# W076Dclone.net
KiCad netlist of a schematic drawn in EAGLE
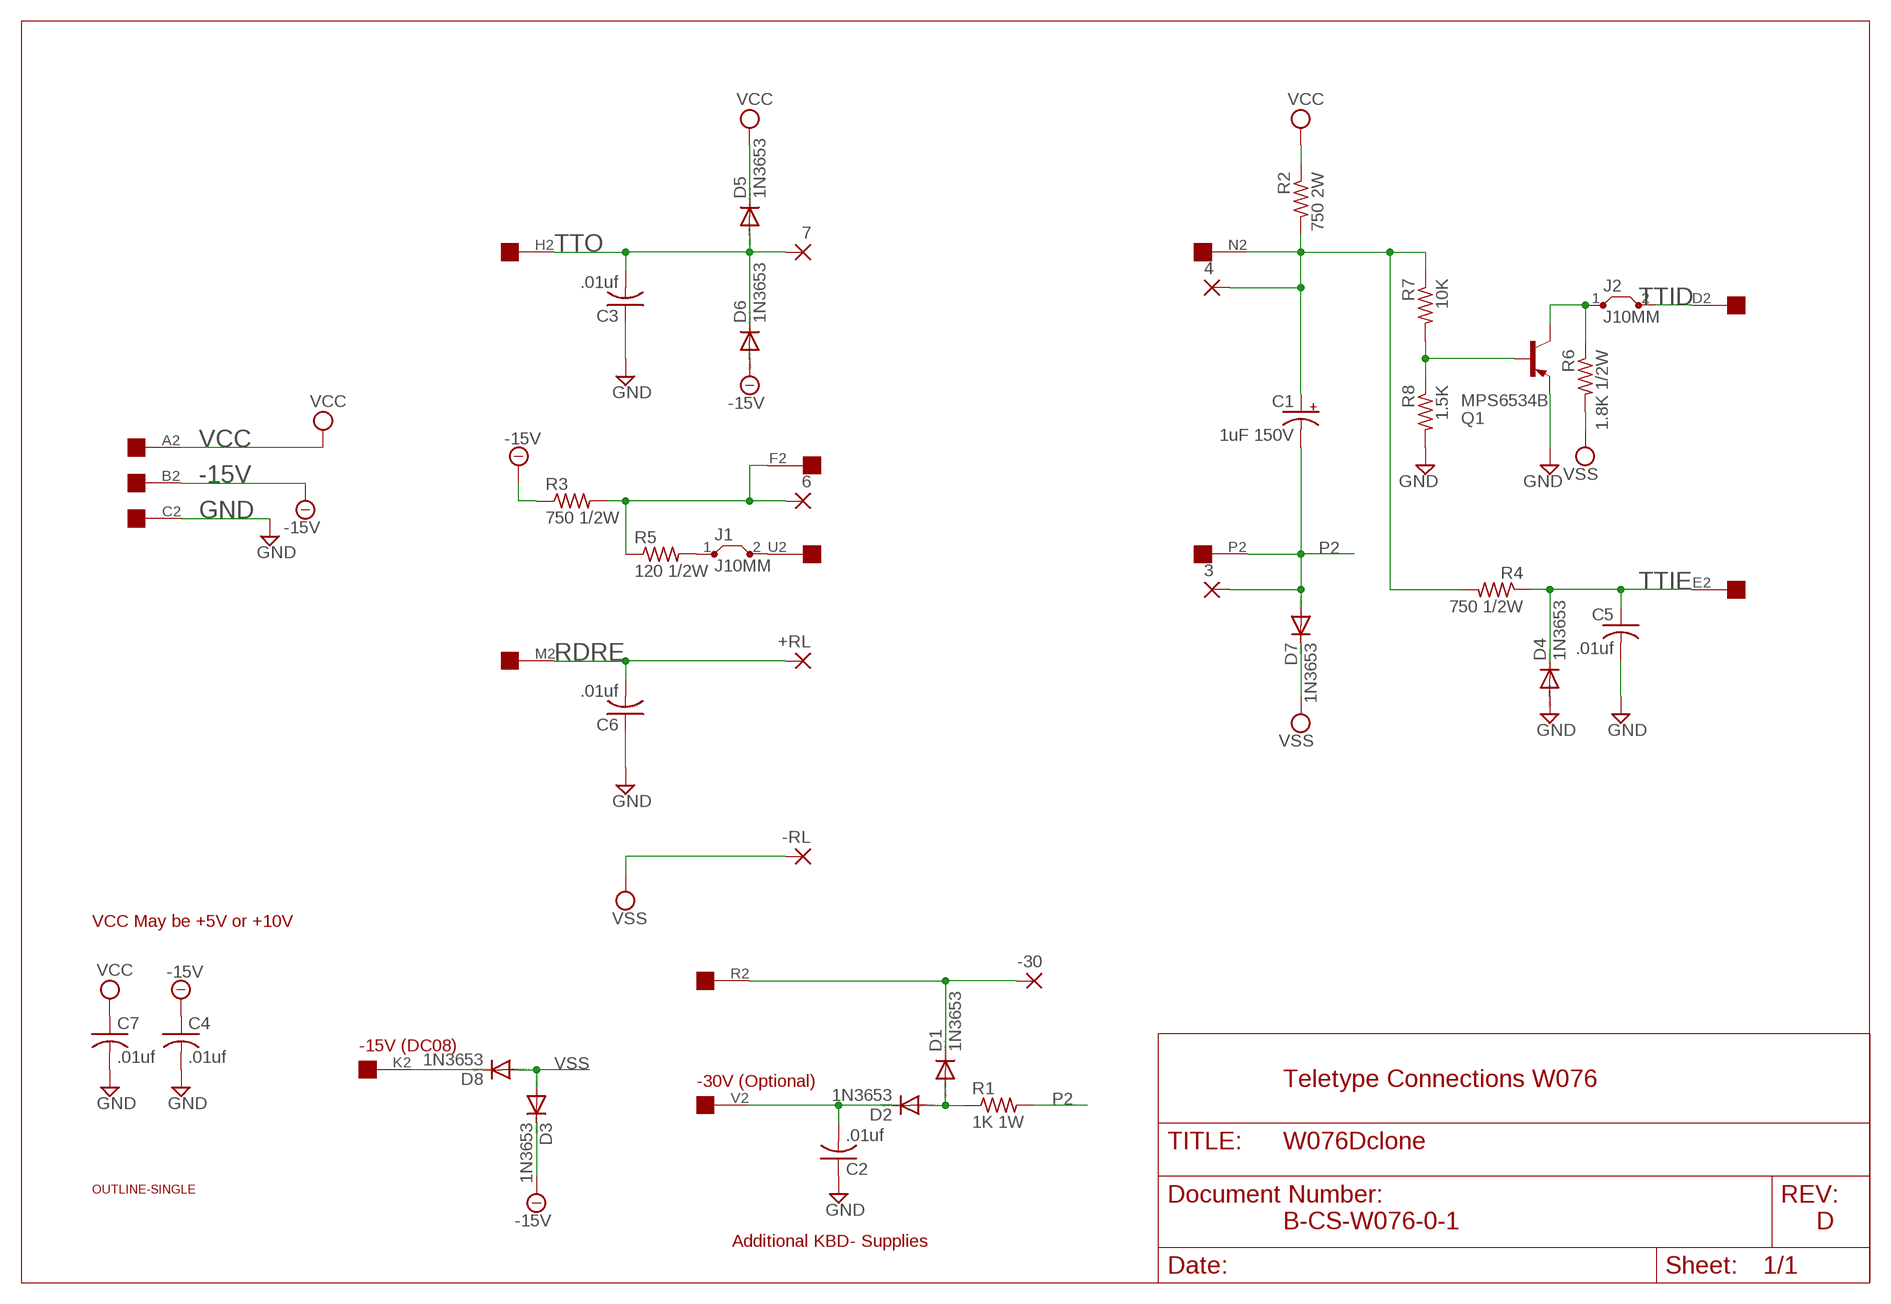
[diagram p0: schematic, sheet 1]

(export (version "E")
  (design (tool "Eeschema 10.0.6"))
  (components
    (comp (ref "+RL")
      (value "2,54/1,0")
      (footprint "eagle-import:2,54_1,0")
      (libsource (lib "eagle-import") (part "2,54/1,0"))
    )
    (comp (ref "-30")
      (value "2,54/1,0")
      (footprint "eagle-import:2,54_1,0")
      (libsource (lib "eagle-import") (part "2,54/1,0"))
    )
    (comp (ref "-RL")
      (value "2,54/1,0")
      (footprint "eagle-import:2,54_1,0")
      (libsource (lib "eagle-import") (part "2,54/1,0"))
    )
    (comp (ref "3")
      (value "2,54/1,0")
      (footprint "eagle-import:2,54_1,0")
      (libsource (lib "eagle-import") (part "2,54/1,0"))
    )
    (comp (ref "4")
      (value "2,54/1,0")
      (footprint "eagle-import:2,54_1,0")
      (libsource (lib "eagle-import") (part "2,54/1,0"))
    )
    (comp (ref "6")
      (value "2,54/1,0")
      (footprint "eagle-import:2,54_1,0")
      (libsource (lib "eagle-import") (part "2,54/1,0"))
    )
    (comp (ref "7")
      (value "2,54/1,0")
      (footprint "eagle-import:2,54_1,0")
      (libsource (lib "eagle-import") (part "2,54/1,0"))
    )
    (comp (ref "C1")
      (value "1uF 150V")
      (footprint "eagle-import:E25-9")
      (libsource (lib "eagle-import") (part "CPOL-USE25-9AXIAL"))
    )
    (comp (ref "C2")
      (value ".01uf")
      (footprint "eagle-import:C050-025X075")
      (libsource (lib "eagle-import") (part "C-US050-025X075"))
    )
    (comp (ref "C3")
      (value ".01uf")
      (footprint "eagle-import:C050-025X075")
      (libsource (lib "eagle-import") (part "C-US050-025X075"))
    )
    (comp (ref "C4")
      (value ".01uf")
      (footprint "eagle-import:C050-025X075")
      (libsource (lib "eagle-import") (part "C-US050-025X075"))
    )
    (comp (ref "C5")
      (value ".01uf")
      (footprint "eagle-import:C050-025X075")
      (libsource (lib "eagle-import") (part "C-US050-025X075"))
    )
    (comp (ref "C6")
      (value ".01uf")
      (footprint "eagle-import:C050-025X075")
      (libsource (lib "eagle-import") (part "C-US050-025X075"))
    )
    (comp (ref "C7")
      (value ".01uf")
      (footprint "eagle-import:C050-025X075")
      (libsource (lib "eagle-import") (part "C-US050-025X075"))
    )
    (comp (ref "D1")
      (value "1N3653")
      (footprint "eagle-import:DO35-10")
      (libsource (lib "eagle-import") (part "1N4148DO35-10"))
    )
    (comp (ref "D2")
      (value "1N3653")
      (footprint "eagle-import:DO35-10")
      (libsource (lib "eagle-import") (part "1N4148DO35-10"))
    )
    (comp (ref "D3")
      (value "1N3653")
      (footprint "eagle-import:DO35-10")
      (libsource (lib "eagle-import") (part "1N4148DO35-10"))
    )
    (comp (ref "D4")
      (value "1N3653")
      (footprint "eagle-import:DO35-10")
      (libsource (lib "eagle-import") (part "1N4148DO35-10"))
    )
    (comp (ref "D5")
      (value "1N3653")
      (footprint "eagle-import:DO35-10")
      (libsource (lib "eagle-import") (part "1N4148DO35-10"))
    )
    (comp (ref "D6")
      (value "1N3653")
      (footprint "eagle-import:DO35-10")
      (libsource (lib "eagle-import") (part "1N4148DO35-10"))
    )
    (comp (ref "D7")
      (value "1N3653")
      (footprint "eagle-import:DO35-10")
      (libsource (lib "eagle-import") (part "1N4148DO35-10"))
    )
    (comp (ref "D8")
      (value "1N3653")
      (footprint "eagle-import:DO35-10")
      (libsource (lib "eagle-import") (part "1N4148DO35-10"))
    )
    (comp (ref "EDGE")
      (value "EDGE-1")
      (footprint "eagle-import:EDGE-CON1")
      (libsource (lib "eagle-import") (part "EDGE-1"))
    )
    (comp (ref "J1")
      (value "J10MM")
      (footprint "eagle-import:10")
      (libsource (lib "eagle-import") (part "J10MM"))
    )
    (comp (ref "J2")
      (value "J10MM")
      (footprint "eagle-import:10")
      (libsource (lib "eagle-import") (part "J10MM"))
    )
    (comp (ref "Q1")
      (value "MPS6534B")
      (footprint "eagle-import:TO39")
      (libsource (lib "eagle-import") (part "2N2904"))
    )
    (comp (ref "R1")
      (value "1K 1W")
      (footprint "eagle-import:P0817_22")
      (libsource (lib "eagle-import") (part "R-US_0817/22"))
    )
    (comp (ref "R2")
      (value "750 2W")
      (footprint "eagle-import:P0817_22")
      (libsource (lib "eagle-import") (part "R-US_0817/22"))
    )
    (comp (ref "R3")
      (value "750 1/2W")
      (footprint "eagle-import:0411_15")
      (libsource (lib "eagle-import") (part "R-US_0411/15"))
    )
    (comp (ref "R4")
      (value "750 1/2W")
      (footprint "eagle-import:0411_15")
      (libsource (lib "eagle-import") (part "R-US_0411/15"))
    )
    (comp (ref "R5")
      (value "120 1/2W")
      (footprint "eagle-import:0411_15")
      (libsource (lib "eagle-import") (part "R-US_0411/15"))
    )
    (comp (ref "R6")
      (value "1.8K 1/2W")
      (footprint "eagle-import:0411_15")
      (libsource (lib "eagle-import") (part "R-US_0411/15"))
    )
    (comp (ref "R7")
      (value "10K")
      (footprint "eagle-import:0411_15")
      (libsource (lib "eagle-import") (part "R-US_0411/15"))
    )
    (comp (ref "R8")
      (value "1.5K")
      (footprint "eagle-import:0411_15")
      (libsource (lib "eagle-import") (part "R-US_0411/15"))
    )
    (comp (ref "U$1")
      (value "OUTLINE-SINGLE")
      (footprint "eagle-import:SINGLE")
      (libsource (lib "eagle-import") (part "OUTLINE-SINGLE"))
    )
  )
  (nets
    (net (code "1") (name "-15V") (class "Default")
      (node (ref "C4") (pin "1") (pinfunction "1_1") (pintype "passive"))
      (node (ref "D3") (pin "C") (pinfunction "C_C") (pintype "passive"))
      (node (ref "D6") (pin "A") (pinfunction "A_A") (pintype "passive"))
      (node (ref "EDGE") (pin "B2") (pinfunction "1_B2") (pintype "bidirectional"))
      (node (ref "R3") (pin "1") (pinfunction "1_1") (pintype "passive"))
    )
    (net (code "2") (name "/P2") (class "Default")
      (node (ref "3") (pin "1") (pinfunction "P_1") (pintype "passive"))
      (node (ref "C1") (pin "-") (pinfunction "-_-") (pintype "passive"))
      (node (ref "D7") (pin "A") (pinfunction "A_A") (pintype "passive"))
      (node (ref "EDGE") (pin "P2") (pinfunction "1_P2") (pintype "bidirectional"))
      (node (ref "R1") (pin "2") (pinfunction "2_2") (pintype "passive"))
    )
    (net (code "3") (name "/RDRE") (class "Default")
      (node (ref "+RL") (pin "1") (pinfunction "P_1") (pintype "passive"))
      (node (ref "C6") (pin "2") (pinfunction "2_2") (pintype "passive"))
      (node (ref "EDGE") (pin "M2") (pinfunction "1_M2") (pintype "bidirectional"))
    )
    (net (code "4") (name "/TTID") (class "Default")
      (node (ref "EDGE") (pin "D2") (pinfunction "1_D2") (pintype "bidirectional"))
      (node (ref "J2") (pin "2") (pinfunction "2_2") (pintype "passive"))
    )
    (net (code "5") (name "/TTIE") (class "Default")
      (node (ref "C5") (pin "1") (pinfunction "1_1") (pintype "passive"))
      (node (ref "D4") (pin "C") (pinfunction "C_C") (pintype "passive"))
      (node (ref "EDGE") (pin "E2") (pinfunction "1_E2") (pintype "bidirectional"))
      (node (ref "R4") (pin "1") (pinfunction "1_1") (pintype "passive"))
    )
    (net (code "6") (name "/TTO") (class "Default")
      (node (ref "7") (pin "1") (pinfunction "P_1") (pintype "passive"))
      (node (ref "C3") (pin "2") (pinfunction "2_2") (pintype "passive"))
      (node (ref "D5") (pin "A") (pinfunction "A_A") (pintype "passive"))
      (node (ref "D6") (pin "C") (pinfunction "C_C") (pintype "passive"))
      (node (ref "EDGE") (pin "H2") (pinfunction "1_H2") (pintype "bidirectional"))
    )
    (net (code "7") (name "GND") (class "Default")
      (node (ref "C2") (pin "1") (pinfunction "1_1") (pintype "passive"))
      (node (ref "C3") (pin "1") (pinfunction "1_1") (pintype "passive"))
      (node (ref "C4") (pin "2") (pinfunction "2_2") (pintype "passive"))
      (node (ref "C5") (pin "2") (pinfunction "2_2") (pintype "passive"))
      (node (ref "C6") (pin "1") (pinfunction "1_1") (pintype "passive"))
      (node (ref "C7") (pin "2") (pinfunction "2_2") (pintype "passive"))
      (node (ref "D4") (pin "A") (pinfunction "A_A") (pintype "passive"))
      (node (ref "EDGE") (pin "C2") (pinfunction "1_C2") (pintype "bidirectional"))
      (node (ref "Q1") (pin "1") (pinfunction "E_1") (pintype "passive"))
      (node (ref "R8") (pin "2") (pinfunction "2_2") (pintype "passive"))
    )
    (net (code "8") (name "Net-(-30-P)") (class "Default")
      (node (ref "-30") (pin "1") (pinfunction "P_1") (pintype "passive"))
      (node (ref "D1") (pin "C") (pinfunction "C_C") (pintype "passive"))
      (node (ref "EDGE") (pin "R2") (pinfunction "1_R2") (pintype "bidirectional"))
    )
    (net (code "9") (name "Net-(4-P)") (class "Default")
      (node (ref "4") (pin "1") (pinfunction "P_1") (pintype "passive"))
      (node (ref "C1") (pin "+") (pinfunction "+_+") (pintype "passive"))
      (node (ref "EDGE") (pin "N2") (pinfunction "1_N2") (pintype "bidirectional"))
      (node (ref "R2") (pin "2") (pinfunction "2_2") (pintype "passive"))
      (node (ref "R4") (pin "2") (pinfunction "2_2") (pintype "passive"))
      (node (ref "R7") (pin "1") (pinfunction "1_1") (pintype "passive"))
    )
    (net (code "10") (name "Net-(6-P)") (class "Default")
      (node (ref "6") (pin "1") (pinfunction "P_1") (pintype "passive"))
      (node (ref "EDGE") (pin "F2") (pinfunction "1_F2") (pintype "bidirectional"))
      (node (ref "R3") (pin "2") (pinfunction "2_2") (pintype "passive"))
      (node (ref "R5") (pin "1") (pinfunction "1_1") (pintype "passive"))
    )
    (net (code "11") (name "Net-(D1-PadA)") (class "Default")
      (node (ref "D1") (pin "A") (pinfunction "A_A") (pintype "passive"))
      (node (ref "D2") (pin "A") (pinfunction "A_A") (pintype "passive"))
      (node (ref "R1") (pin "1") (pinfunction "1_1") (pintype "passive"))
    )
    (net (code "12") (name "Net-(EDGEI-1)") (class "Default")
      (node (ref "D8") (pin "C") (pinfunction "C_C") (pintype "passive"))
      (node (ref "EDGE") (pin "K2") (pinfunction "1_K2") (pintype "bidirectional"))
    )
    (net (code "13") (name "Net-(EDGEQ-1)") (class "Default")
      (node (ref "EDGE") (pin "U2") (pinfunction "1_U2") (pintype "bidirectional"))
      (node (ref "J1") (pin "2") (pinfunction "2_2") (pintype "passive"))
    )
    (net (code "14") (name "Net-(EDGER-1)") (class "Default")
      (node (ref "C2") (pin "2") (pinfunction "2_2") (pintype "passive"))
      (node (ref "D2") (pin "C") (pinfunction "C_C") (pintype "passive"))
      (node (ref "EDGE") (pin "V2") (pinfunction "1_V2") (pintype "bidirectional"))
    )
    (net (code "15") (name "Net-(J1-Pad1)") (class "Default")
      (node (ref "J1") (pin "1") (pinfunction "1_1") (pintype "passive"))
      (node (ref "R5") (pin "2") (pinfunction "2_2") (pintype "passive"))
    )
    (net (code "16") (name "Net-(Q1-B)") (class "Default")
      (node (ref "Q1") (pin "2") (pinfunction "B_2") (pintype "passive"))
      (node (ref "R7") (pin "2") (pinfunction "2_2") (pintype "passive"))
      (node (ref "R8") (pin "1") (pinfunction "1_1") (pintype "passive"))
    )
    (net (code "17") (name "Net-(Q1-C)") (class "Default")
      (node (ref "J2") (pin "1") (pinfunction "1_1") (pintype "passive"))
      (node (ref "Q1") (pin "3") (pinfunction "C_3") (pintype "passive"))
      (node (ref "R6") (pin "1") (pinfunction "1_1") (pintype "passive"))
    )
    (net (code "18") (name "VCC") (class "Default")
      (node (ref "C7") (pin "1") (pinfunction "1_1") (pintype "passive"))
      (node (ref "D5") (pin "C") (pinfunction "C_C") (pintype "passive"))
      (node (ref "EDGE") (pin "A2") (pinfunction "1_A2") (pintype "bidirectional"))
      (node (ref "R2") (pin "1") (pinfunction "1_1") (pintype "passive"))
    )
    (net (code "19") (name "VSS") (class "Default")
      (node (ref "-RL") (pin "1") (pinfunction "P_1") (pintype "passive"))
      (node (ref "D3") (pin "A") (pinfunction "A_A") (pintype "passive"))
      (node (ref "D7") (pin "C") (pinfunction "C_C") (pintype "passive"))
      (node (ref "D8") (pin "A") (pinfunction "A_A") (pintype "passive"))
      (node (ref "R6") (pin "2") (pinfunction "2_2") (pintype "passive"))
    )
  )
)
